# Sheet2.net
KiCad netlist of a schematic drawn in Altium Designer
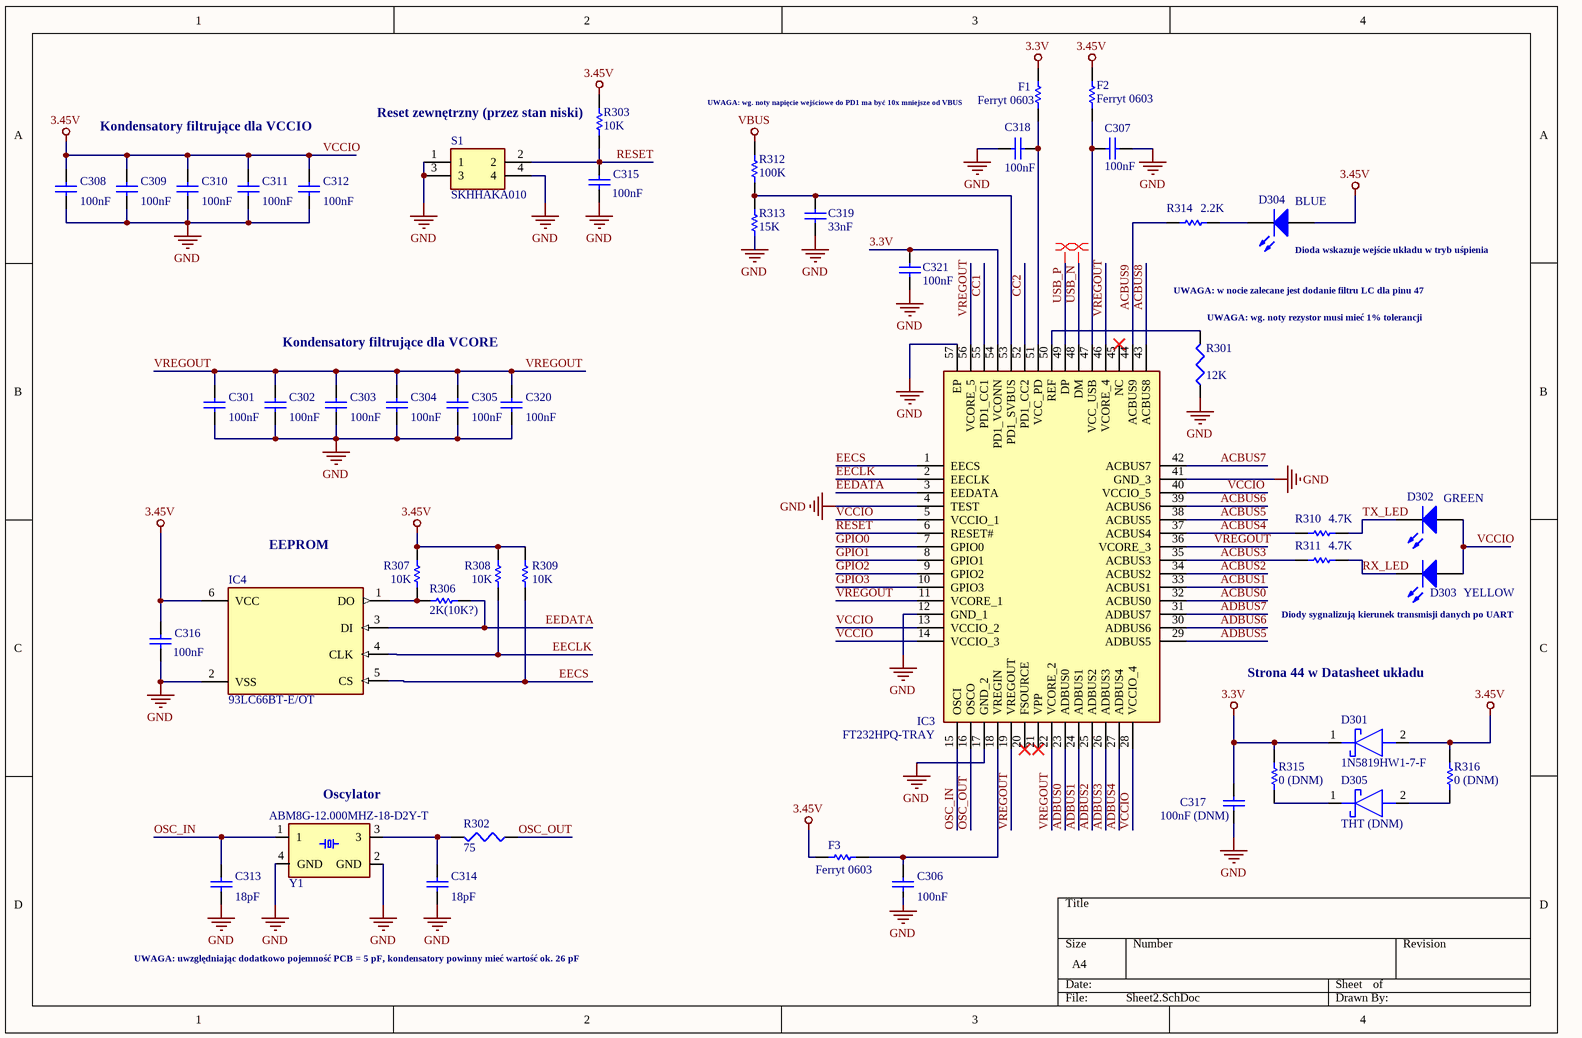
[diagram p0: Sheet2.SchDoc]

(export (version "E")
  (design (tool "Eeschema 10.0.6"))
  (components
    (comp (ref "C301")
      (value "100nF")
      (footprint "1608[0603]")
      (description "Capacitor (Semiconductor SIM Model)")
      (fields (field (name "Comment") "Cap Semi") (field (name "PUBLISHER") "Altium Limited"))
      (libsource (lib "Miscellaneous Devices") (part "Cap Semi"))
    )
    (comp (ref "C302")
      (value "100nF")
      (footprint "1608[0603]")
      (description "Capacitor (Semiconductor SIM Model)")
      (fields (field (name "Comment") "Cap Semi") (field (name "PUBLISHER") "Altium Limited"))
      (libsource (lib "Miscellaneous Devices") (part "Cap Semi"))
    )
    (comp (ref "C303")
      (value "100nF")
      (footprint "1608[0603]")
      (description "Capacitor (Semiconductor SIM Model)")
      (fields (field (name "Comment") "Cap Semi") (field (name "PUBLISHER") "Altium Limited"))
      (libsource (lib "Miscellaneous Devices") (part "Cap Semi"))
    )
    (comp (ref "C304")
      (value "100nF")
      (footprint "1608[0603]")
      (description "Capacitor (Semiconductor SIM Model)")
      (fields (field (name "Comment") "Cap Semi") (field (name "PUBLISHER") "Altium Limited"))
      (libsource (lib "Miscellaneous Devices") (part "Cap Semi"))
    )
    (comp (ref "C305")
      (value "100nF")
      (footprint "1608[0603]")
      (description "Capacitor (Semiconductor SIM Model)")
      (fields (field (name "Comment") "Cap Semi") (field (name "PUBLISHER") "Altium Limited"))
      (libsource (lib "Miscellaneous Devices") (part "Cap Semi"))
    )
    (comp (ref "C306")
      (value "100nF")
      (footprint "1608[0603]")
      (description "Capacitor (Semiconductor SIM Model)")
      (fields (field (name "Comment") "Cap Semi") (field (name "PUBLISHER") "Altium Limited"))
      (libsource (lib "Miscellaneous Devices") (part "Cap Semi"))
    )
    (comp (ref "C307")
      (value "100nF")
      (footprint "1608[0603]")
      (description "Capacitor (Semiconductor SIM Model)")
      (fields (field (name "Comment") "Cap Semi") (field (name "PUBLISHER") "Altium Limited"))
      (libsource (lib "Miscellaneous Devices") (part "Cap Semi"))
    )
    (comp (ref "C308")
      (value "100nF")
      (footprint "1608[0603]")
      (description "Capacitor (Semiconductor SIM Model)")
      (fields (field (name "Comment") "Cap Semi") (field (name "PUBLISHER") "Altium Limited"))
      (libsource (lib "Miscellaneous Devices") (part "Cap Semi"))
    )
    (comp (ref "C309")
      (value "100nF")
      (footprint "1608[0603]")
      (description "Capacitor (Semiconductor SIM Model)")
      (fields (field (name "Comment") "Cap Semi") (field (name "PUBLISHER") "Altium Limited"))
      (libsource (lib "Miscellaneous Devices") (part "Cap Semi"))
    )
    (comp (ref "C310")
      (value "100nF")
      (footprint "1608[0603]")
      (description "Capacitor (Semiconductor SIM Model)")
      (fields (field (name "Comment") "Cap Semi") (field (name "PUBLISHER") "Altium Limited"))
      (libsource (lib "Miscellaneous Devices") (part "Cap Semi"))
    )
    (comp (ref "C311")
      (value "100nF")
      (footprint "1608[0603]")
      (description "Capacitor (Semiconductor SIM Model)")
      (fields (field (name "Comment") "Cap Semi") (field (name "PUBLISHER") "Altium Limited"))
      (libsource (lib "Miscellaneous Devices") (part "Cap Semi"))
    )
    (comp (ref "C312")
      (value "100nF")
      (footprint "1608[0603]")
      (description "Capacitor (Semiconductor SIM Model)")
      (fields (field (name "Comment") "Cap Semi") (field (name "PUBLISHER") "Altium Limited"))
      (libsource (lib "Miscellaneous Devices") (part "Cap Semi"))
    )
    (comp (ref "C313")
      (value "18pF")
      (footprint "1608[0603]")
      (description "Capacitor (Semiconductor SIM Model)")
      (fields (field (name "Comment") "Cap Semi") (field (name "PUBLISHER") "Altium Limited"))
      (libsource (lib "Miscellaneous Devices") (part "Cap Semi"))
    )
    (comp (ref "C314")
      (value "18pF")
      (footprint "1608[0603]")
      (description "Capacitor (Semiconductor SIM Model)")
      (fields (field (name "Comment") "Cap Semi") (field (name "PUBLISHER") "Altium Limited"))
      (libsource (lib "Miscellaneous Devices") (part "Cap Semi"))
    )
    (comp (ref "C315")
      (value "100nF")
      (footprint "1608[0603]")
      (description "Capacitor (Semiconductor SIM Model)")
      (fields (field (name "Comment") "Cap Semi") (field (name "PUBLISHER") "Altium Limited"))
      (libsource (lib "Miscellaneous Devices") (part "Cap Semi"))
    )
    (comp (ref "C316")
      (value "100nF")
      (footprint "1608[0603]")
      (description "Capacitor (Semiconductor SIM Model)")
      (fields (field (name "Comment") "Cap Semi") (field (name "PUBLISHER") "Altium Limited"))
      (libsource (lib "Miscellaneous Devices") (part "Cap Semi"))
    )
    (comp (ref "C317")
      (value "100nF (DNM)")
      (footprint "1608[0603]")
      (description "Capacitor (Semiconductor SIM Model)")
      (fields (field (name "Comment") "Cap Semi") (field (name "PUBLISHER") "Altium Limited"))
      (libsource (lib "Miscellaneous Devices") (part "Cap Semi"))
    )
    (comp (ref "C318")
      (value "100nF")
      (footprint "1608[0603]")
      (description "Capacitor (Semiconductor SIM Model)")
      (fields (field (name "Comment") "Cap Semi") (field (name "PUBLISHER") "Altium Limited"))
      (libsource (lib "Miscellaneous Devices") (part "Cap Semi"))
    )
    (comp (ref "C319")
      (value "33nF")
      (footprint "1608[0603]")
      (description "Capacitor (Semiconductor SIM Model)")
      (fields (field (name "Comment") "Cap Semi") (field (name "PUBLISHER") "Altium Limited"))
      (libsource (lib "Miscellaneous Devices") (part "Cap Semi"))
    )
    (comp (ref "C320")
      (value "100nF")
      (footprint "1608[0603]")
      (description "Capacitor (Semiconductor SIM Model)")
      (fields (field (name "Comment") "Cap Semi") (field (name "PUBLISHER") "Altium Limited"))
      (libsource (lib "Miscellaneous Devices") (part "Cap Semi"))
    )
    (comp (ref "C321")
      (value "100nF")
      (footprint "1608[0603]")
      (description "Capacitor (Semiconductor SIM Model)")
      (fields (field (name "Comment") "Cap Semi") (field (name "PUBLISHER") "Altium Limited"))
      (libsource (lib "Miscellaneous Devices") (part "Cap Semi"))
    )
    (comp (ref "D301")
      (value "1N5819HW1-7-F")
      (footprint "SODFL3518X115N")
      (description "Schottky Diode")
      (fields (field (name "MOUSER PART NUMBER") "621-1N5819HW1-7-F"))
      (libsource (lib "Schlib1") (part "1N5819HW1-7-F"))
    )
    (comp (ref "D302")
      (value "GREEN")
      (footprint "LEDC2012X80N")
      (description "Typical RED, GREEN, YELLOW, AMBER GaAs LED")
      (fields (field (name "PUBLISHER") "Altium Limited"))
      (libsource (lib "Miscellaneous Devices") (part "LED2"))
    )
    (comp (ref "D303")
      (value "YELLOW")
      (footprint "LEDC2012X80N")
      (description "Typical RED, GREEN, YELLOW, AMBER GaAs LED")
      (fields (field (name "PUBLISHER") "Altium Limited"))
      (libsource (lib "Miscellaneous Devices") (part "LED2"))
    )
    (comp (ref "D304")
      (value "BLUE")
      (footprint "LEDC2012X80N")
      (description "Typical RED, GREEN, YELLOW, AMBER GaAs LED")
      (fields (field (name "PUBLISHER") "Altium Limited"))
      (libsource (lib "Miscellaneous Devices") (part "LED2"))
    )
    (comp (ref "D305")
      (value "THT (DNM)")
      (footprint "DIOAD1796W86L628D292")
      (description "Schottky Diode")
      (fields
        (field (name "MANUFACTURER_PART_NUMBER") "1N5819HW1-7-F")
        (field (name "MOUSER PART NUMBER") "621-1N5819HW1-7-F")
      )
      (libsource (lib "Schlib1") (part "1N5819HW1-7-F"))
    )
    (comp (ref "F1")
      (value "Ferryt 0603")
      (footprint "RESC1608X55N")
      (description "Small resistor symbol 0603")
      (fields
        (field (name "MANUFACTURER") "Panasonic")
        (field (name "MANUFACTURER PART NUMBER") "ERJ-2GEJ510X")
      )
      (libsource (lib "Schlib1") (part "Resistor 0603"))
    )
    (comp (ref "F2")
      (value "Ferryt 0603")
      (footprint "RESC1608X55N")
      (description "Small resistor symbol 0603")
      (fields
        (field (name "MANUFACTURER") "Panasonic")
        (field (name "MANUFACTURER PART NUMBER") "ERJ-2GEJ510X")
      )
      (libsource (lib "Schlib1") (part "Resistor 0603"))
    )
    (comp (ref "F3")
      (value "Ferryt 0603")
      (footprint "RESC1608X55N")
      (description "Small resistor symbol 0603")
      (fields
        (field (name "MANUFACTURER") "Panasonic")
        (field (name "MANUFACTURER PART NUMBER") "ERJ-2GEJ510X")
      )
      (libsource (lib "Schlib1") (part "Resistor 0603"))
    )
    (comp (ref "IC3")
      (value "FT232HPQ-TRAY")
      (footprint "QFN50P800X800X90-57N-D")
      (description "Integrated Circuit")
      (fields (field (name "MOUSER PART NUMBER") "895-FT232HPQ-TRAY"))
      (libsource (lib "Schlib1") (part "FT232HPQ-TRAY"))
    )
    (comp (ref "IC4")
      (value "93LC66BT-E/OT")
      (footprint "SOT95P280X145-6N")
      (description "Microwire Compatible Serial EEPROM")
      (libsource (lib "Schlib1") (part "93LC66BT-E/OT"))
    )
    (comp (ref "R301")
      (value "12K")
      (footprint "RESC1608X55N")
      (description "Resistor")
      (fields (field (name "Comment") "Res3") (field (name "PUBLISHER") "Altium Limited"))
      (libsource (lib "Miscellaneous Devices") (part "Res3"))
    )
    (comp (ref "R302")
      (value "75")
      (footprint "RESC1608X55N")
      (description "Resistor")
      (fields (field (name "Comment") "Res3") (field (name "PUBLISHER") "Altium Limited"))
      (libsource (lib "Miscellaneous Devices") (part "Res3"))
    )
    (comp (ref "R303")
      (value "10K")
      (footprint "RESC1608X55N")
      (description "Small resistor symbol 0603")
      (fields
        (field (name "MANUFACTURER") "Panasonic")
        (field (name "MANUFACTURER PART NUMBER") "ERJ-2GEJ510X")
      )
      (libsource (lib "Schlib1") (part "Resistor 0603"))
    )
    (comp (ref "R306")
      (value "2K(10K?)")
      (footprint "RESC1608X55N")
      (description "Small resistor symbol 0603")
      (fields
        (field (name "MANUFACTURER") "Panasonic")
        (field (name "MANUFACTURER PART NUMBER") "ERJ-2GEJ510X")
      )
      (libsource (lib "Schlib1") (part "Resistor 0603"))
    )
    (comp (ref "R307")
      (value "10K")
      (footprint "RESC1608X55N")
      (description "Small resistor symbol 0603")
      (fields
        (field (name "MANUFACTURER") "Panasonic")
        (field (name "MANUFACTURER PART NUMBER") "ERJ-2GEJ510X")
      )
      (libsource (lib "Schlib1") (part "Resistor 0603"))
    )
    (comp (ref "R308")
      (value "10K")
      (footprint "RESC1608X55N")
      (description "Small resistor symbol 0603")
      (fields
        (field (name "MANUFACTURER") "Panasonic")
        (field (name "MANUFACTURER PART NUMBER") "ERJ-2GEJ510X")
      )
      (libsource (lib "Schlib1") (part "Resistor 0603"))
    )
    (comp (ref "R309")
      (value "10K")
      (footprint "RESC1608X55N")
      (description "Small resistor symbol 0603")
      (fields
        (field (name "MANUFACTURER") "Panasonic")
        (field (name "MANUFACTURER PART NUMBER") "ERJ-2GEJ510X")
      )
      (libsource (lib "Schlib1") (part "Resistor 0603"))
    )
    (comp (ref "R310")
      (value "4.7K")
      (footprint "RESC1608X55N")
      (description "Small resistor symbol 0603")
      (fields
        (field (name "MANUFACTURER") "Panasonic")
        (field (name "MANUFACTURER PART NUMBER") "ERJ-2GEJ510X")
      )
      (libsource (lib "Schlib1") (part "Resistor 0603"))
    )
    (comp (ref "R311")
      (value "4.7K")
      (footprint "RESC1608X55N")
      (description "Small resistor symbol 0603")
      (fields
        (field (name "MANUFACTURER") "Panasonic")
        (field (name "MANUFACTURER PART NUMBER") "ERJ-2GEJ510X")
      )
      (libsource (lib "Schlib1") (part "Resistor 0603"))
    )
    (comp (ref "R312")
      (value "100K")
      (footprint "RESC1608X55N")
      (description "Small resistor symbol 0603")
      (fields
        (field (name "MANUFACTURER") "Panasonic")
        (field (name "MANUFACTURER PART NUMBER") "ERJ-2GEJ510X")
      )
      (libsource (lib "Schlib1") (part "Resistor 0603"))
    )
    (comp (ref "R313")
      (value "15K")
      (footprint "RESC1608X55N")
      (description "Small resistor symbol 0603")
      (fields
        (field (name "MANUFACTURER") "Panasonic")
        (field (name "MANUFACTURER PART NUMBER") "ERJ-2GEJ510X")
      )
      (libsource (lib "Schlib1") (part "Resistor 0603"))
    )
    (comp (ref "R314")
      (value "2.2K")
      (footprint "RESC1608X55N")
      (description "Small resistor symbol 0603")
      (fields
        (field (name "MANUFACTURER") "Panasonic")
        (field (name "MANUFACTURER PART NUMBER") "ERJ-2GEJ510X")
      )
      (libsource (lib "Schlib1") (part "Resistor 0603"))
    )
    (comp (ref "R315")
      (value "0 (DNM)")
      (footprint "RESC1608X55N")
      (description "Small resistor symbol 0603")
      (fields
        (field (name "MANUFACTURER") "Panasonic")
        (field (name "MANUFACTURER PART NUMBER") "ERJ-2GEJ510X")
      )
      (libsource (lib "Schlib1") (part "Resistor 0603"))
    )
    (comp (ref "R316")
      (value "0 (DNM)")
      (footprint "RESC1608X55N")
      (description "Small resistor symbol 0603")
      (fields
        (field (name "MANUFACTURER") "Panasonic")
        (field (name "MANUFACTURER PART NUMBER") "ERJ-2GEJ510X")
      )
      (libsource (lib "Schlib1") (part "Resistor 0603"))
    )
    (comp (ref "S1")
      (value "SKHHAKA010")
      (footprint "SKHHALA010")
      (description "Switch")
      (fields (field (name "MOUSER PART NUMBER") "688-SKHHAK"))
      (libsource (lib "Schlib1") (part "SKHHAKA010"))
    )
    (comp (ref "Y1")
      (value "ABM8G-12.000MHZ-18-D2Y-T")
      (footprint "OSCSC320X250X100N")
      (description "12MHz Â±20ppm Crystal 18pF 120 Ohms 4-SMD, No Lead")
      (fields (field (name "MF") "Abracon") (field (name "DIGI-KEY_PART_NUMBER") "535-10261-1-ND"))
      (libsource (lib "Schlib1") (part "ABM8G-12.000MHZ-18-D2Y-T"))
    )
  )
  (nets
    (net (code "1") (name "/ACBUS0") (class "Default")
      (node (ref "IC3") (pin "32") (pinfunction "ACBUS0_32") (pintype "passive"))
    )
    (net (code "2") (name "/ACBUS1") (class "Default")
      (node (ref "IC3") (pin "33") (pinfunction "ACBUS1_33") (pintype "passive"))
    )
    (net (code "3") (name "/ACBUS2") (class "Default")
      (node (ref "IC3") (pin "34") (pinfunction "ACBUS2_34") (pintype "passive"))
    )
    (net (code "4") (name "/ACBUS3") (class "Default")
      (node (ref "IC3") (pin "35") (pinfunction "ACBUS3_35") (pintype "passive"))
      (node (ref "R311") (pin "1") (pinfunction "1_1") (pintype "passive"))
    )
    (net (code "5") (name "/ACBUS4") (class "Default")
      (node (ref "IC3") (pin "37") (pinfunction "ACBUS4_37") (pintype "passive"))
      (node (ref "R310") (pin "1") (pinfunction "1_1") (pintype "passive"))
    )
    (net (code "6") (name "/ACBUS5") (class "Default")
      (node (ref "IC3") (pin "38") (pinfunction "ACBUS5_38") (pintype "passive"))
    )
    (net (code "7") (name "/ACBUS6") (class "Default")
      (node (ref "IC3") (pin "39") (pinfunction "ACBUS6_39") (pintype "passive"))
    )
    (net (code "8") (name "/ACBUS7") (class "Default")
      (node (ref "IC3") (pin "42") (pinfunction "ACBUS7_42") (pintype "passive"))
    )
    (net (code "9") (name "/ACBUS8") (class "Default")
      (node (ref "IC3") (pin "43") (pinfunction "ACBUS8_43") (pintype "passive"))
    )
    (net (code "10") (name "/ACBUS9") (class "Default")
      (node (ref "IC3") (pin "44") (pinfunction "ACBUS9_44") (pintype "passive"))
      (node (ref "R314") (pin "1") (pinfunction "1_1") (pintype "passive"))
    )
    (net (code "11") (name "/ADBUS0") (class "Default")
      (node (ref "IC3") (pin "23") (pinfunction "ADBUS0_23") (pintype "passive"))
    )
    (net (code "12") (name "/ADBUS1") (class "Default")
      (node (ref "IC3") (pin "24") (pinfunction "ADBUS1_24") (pintype "passive"))
    )
    (net (code "13") (name "/ADBUS2") (class "Default")
      (node (ref "IC3") (pin "25") (pinfunction "ADBUS2_25") (pintype "passive"))
    )
    (net (code "14") (name "/ADBUS3") (class "Default")
      (node (ref "IC3") (pin "26") (pinfunction "ADBUS3_26") (pintype "passive"))
    )
    (net (code "15") (name "/ADBUS4") (class "Default")
      (node (ref "IC3") (pin "27") (pinfunction "ADBUS4_27") (pintype "passive"))
    )
    (net (code "16") (name "/ADBUS5") (class "Default")
      (node (ref "IC3") (pin "29") (pinfunction "ADBUS5_29") (pintype "passive"))
    )
    (net (code "17") (name "/ADBUS6") (class "Default")
      (node (ref "IC3") (pin "30") (pinfunction "ADBUS6_30") (pintype "passive"))
    )
    (net (code "18") (name "/ADBUS7") (class "Default")
      (node (ref "IC3") (pin "31") (pinfunction "ADBUS7_31") (pintype "passive"))
    )
    (net (code "19") (name "/CC1") (class "Default")
      (node (ref "IC3") (pin "55") (pinfunction "PD1_CC1_55") (pintype "passive"))
    )
    (net (code "20") (name "/CC2") (class "Default")
      (node (ref "IC3") (pin "52") (pinfunction "PD1_CC2_52") (pintype "passive"))
    )
    (net (code "21") (name "/EECLK") (class "Default")
      (node (ref "IC3") (pin "2") (pinfunction "EECLK_2") (pintype "passive"))
      (node (ref "IC4") (pin "4") (pinfunction "CLK_4") (pintype "input"))
      (node (ref "R308") (pin "2") (pinfunction "2_2") (pintype "passive"))
    )
    (net (code "22") (name "/EECS") (class "Default")
      (node (ref "IC3") (pin "1") (pinfunction "EECS_1") (pintype "passive"))
      (node (ref "IC4") (pin "5") (pinfunction "CS_5") (pintype "input"))
      (node (ref "R309") (pin "2") (pinfunction "2_2") (pintype "passive"))
    )
    (net (code "23") (name "/EEDATA") (class "Default")
      (node (ref "IC3") (pin "3") (pinfunction "EEDATA_3") (pintype "passive"))
      (node (ref "IC4") (pin "3") (pinfunction "DI_3") (pintype "input"))
      (node (ref "R306") (pin "2") (pinfunction "2_2") (pintype "passive"))
    )
    (net (code "24") (name "/GPIO0") (class "Default")
      (node (ref "IC3") (pin "7") (pinfunction "GPIO0_7") (pintype "passive"))
    )
    (net (code "25") (name "/GPIO1") (class "Default")
      (node (ref "IC3") (pin "8") (pinfunction "GPIO1_8") (pintype "passive"))
    )
    (net (code "26") (name "/GPIO2") (class "Default")
      (node (ref "IC3") (pin "9") (pinfunction "GPIO2_9") (pintype "passive"))
    )
    (net (code "27") (name "/GPIO3") (class "Default")
      (node (ref "IC3") (pin "10") (pinfunction "GPIO3_10") (pintype "passive"))
    )
    (net (code "28") (name "/OSC_IN") (class "Default")
      (node (ref "C313") (pin "2") (pinfunction "2_2") (pintype "passive"))
      (node (ref "IC3") (pin "15") (pinfunction "OSCI_15") (pintype "passive"))
      (node (ref "Y1") (pin "1") (pinfunction "1_1") (pintype "passive"))
    )
    (net (code "29") (name "/OSC_OUT") (class "Default")
      (node (ref "IC3") (pin "16") (pinfunction "OSCO_16") (pintype "passive"))
      (node (ref "R302") (pin "1") (pinfunction "1_1") (pintype "passive"))
    )
    (net (code "30") (name "/RESET") (class "Default")
      (node (ref "C315") (pin "1") (pinfunction "1_1") (pintype "passive"))
      (node (ref "IC3") (pin "6") (pinfunction "RESET#_6") (pintype "passive"))
      (node (ref "R303") (pin "1") (pinfunction "1_1") (pintype "passive"))
      (node (ref "S1") (pin "2") (pinfunction "2_2") (pintype "passive"))
    )
    (net (code "31") (name "/RX_LED") (class "Default")
      (node (ref "D303") (pin "2") (pinfunction "K_2") (pintype "passive"))
      (node (ref "R311") (pin "2") (pinfunction "2_2") (pintype "passive"))
    )
    (net (code "32") (name "/TX_LED") (class "Default")
      (node (ref "D302") (pin "2") (pinfunction "K_2") (pintype "passive"))
      (node (ref "R310") (pin "2") (pinfunction "2_2") (pintype "passive"))
    )
    (net (code "33") (name "/USB_N") (class "Default")
      (node (ref "IC3") (pin "48") (pinfunction "DM_48") (pintype "passive"))
    )
    (net (code "34") (name "/USB_P") (class "Default")
      (node (ref "IC3") (pin "49") (pinfunction "DP_49") (pintype "passive"))
    )
    (net (code "35") (name "/VREGOUT") (class "Default")
      (node (ref "C301") (pin "2") (pinfunction "2_2") (pintype "passive"))
      (node (ref "C302") (pin "2") (pinfunction "2_2") (pintype "passive"))
      (node (ref "C303") (pin "2") (pinfunction "2_2") (pintype "passive"))
      (node (ref "C304") (pin "2") (pinfunction "2_2") (pintype "passive"))
      (node (ref "C305") (pin "2") (pinfunction "2_2") (pintype "passive"))
      (node (ref "C320") (pin "2") (pinfunction "2_2") (pintype "passive"))
      (node (ref "IC3") (pin "11") (pinfunction "VCORE_1_11") (pintype "passive"))
      (node (ref "IC3") (pin "19") (pinfunction "VREGOUT_19") (pintype "passive"))
      (node (ref "IC3") (pin "22") (pinfunction "VCORE_2_22") (pintype "passive"))
      (node (ref "IC3") (pin "36") (pinfunction "VCORE_3_36") (pintype "passive"))
      (node (ref "IC3") (pin "46") (pinfunction "VCORE_4_46") (pintype "passive"))
      (node (ref "IC3") (pin "56") (pinfunction "VCORE_5_56") (pintype "passive"))
    )
    (net (code "36") (name "3.3V") (class "Default")
      (node (ref "C317") (pin "1") (pinfunction "1_1") (pintype "passive"))
      (node (ref "C321") (pin "2") (pinfunction "2_2") (pintype "passive"))
      (node (ref "D301") (pin "1") (pinfunction "K_1") (pintype "passive"))
      (node (ref "F1") (pin "2") (pinfunction "2_2") (pintype "passive"))
      (node (ref "IC3") (pin "54") (pinfunction "PD1_VCONN_54") (pintype "passive"))
      (node (ref "R315") (pin "2") (pinfunction "2_2") (pintype "passive"))
    )
    (net (code "37") (name "3.45V") (class "Default")
      (node (ref "C308") (pin "2") (pinfunction "2_2") (pintype "passive"))
      (node (ref "C309") (pin "2") (pinfunction "2_2") (pintype "passive"))
      (node (ref "C310") (pin "2") (pinfunction "2_2") (pintype "passive"))
      (node (ref "C311") (pin "2") (pinfunction "2_2") (pintype "passive"))
      (node (ref "C312") (pin "2") (pinfunction "2_2") (pintype "passive"))
      (node (ref "C316") (pin "1") (pinfunction "1_1") (pintype "passive"))
      (node (ref "D301") (pin "2") (pinfunction "A_2") (pintype "passive"))
      (node (ref "D302") (pin "1") (pinfunction "A_1") (pintype "passive"))
      (node (ref "D303") (pin "1") (pinfunction "A_1") (pintype "passive"))
      (node (ref "D304") (pin "1") (pinfunction "A_1") (pintype "passive"))
      (node (ref "F2") (pin "1") (pinfunction "1_1") (pintype "passive"))
      (node (ref "F3") (pin "1") (pinfunction "1_1") (pintype "passive"))
      (node (ref "IC3") (pin "13") (pinfunction "VCCIO_2_13") (pintype "passive"))
      (node (ref "IC3") (pin "14") (pinfunction "VCCIO_3_14") (pintype "passive"))
      (node (ref "IC3") (pin "28") (pinfunction "VCCIO_4_28") (pintype "passive"))
      (node (ref "IC3") (pin "40") (pinfunction "VCCIO_5_40") (pintype "passive"))
      (node (ref "IC3") (pin "5") (pinfunction "VCCIO_1_5") (pintype "passive"))
      (node (ref "IC4") (pin "6") (pinfunction "VCC_6") (pintype "power_in"))
      (node (ref "R303") (pin "2") (pinfunction "2_2") (pintype "passive"))
      (node (ref "R307") (pin "1") (pinfunction "1_1") (pintype "passive"))
      (node (ref "R308") (pin "1") (pinfunction "1_1") (pintype "passive"))
      (node (ref "R309") (pin "1") (pinfunction "1_1") (pintype "passive"))
      (node (ref "R316") (pin "2") (pinfunction "2_2") (pintype "passive"))
    )
    (net (code "38") (name "GND") (class "Default")
      (node (ref "C301") (pin "1") (pinfunction "1_1") (pintype "passive"))
      (node (ref "C302") (pin "1") (pinfunction "1_1") (pintype "passive"))
      (node (ref "C303") (pin "1") (pinfunction "1_1") (pintype "passive"))
      (node (ref "C304") (pin "1") (pinfunction "1_1") (pintype "passive"))
      (node (ref "C305") (pin "1") (pinfunction "1_1") (pintype "passive"))
      (node (ref "C306") (pin "1") (pinfunction "1_1") (pintype "passive"))
      (node (ref "C307") (pin "2") (pinfunction "2_2") (pintype "passive"))
      (node (ref "C308") (pin "1") (pinfunction "1_1") (pintype "passive"))
      (node (ref "C309") (pin "1") (pinfunction "1_1") (pintype "passive"))
      (node (ref "C310") (pin "1") (pinfunction "1_1") (pintype "passive"))
      (node (ref "C311") (pin "1") (pinfunction "1_1") (pintype "passive"))
      (node (ref "C312") (pin "1") (pinfunction "1_1") (pintype "passive"))
      (node (ref "C313") (pin "1") (pinfunction "1_1") (pintype "passive"))
      (node (ref "C314") (pin "1") (pinfunction "1_1") (pintype "passive"))
      (node (ref "C315") (pin "2") (pinfunction "2_2") (pintype "passive"))
      (node (ref "C316") (pin "2") (pinfunction "2_2") (pintype "passive"))
      (node (ref "C317") (pin "2") (pinfunction "2_2") (pintype "passive"))
      (node (ref "C318") (pin "1") (pinfunction "1_1") (pintype "passive"))
      (node (ref "C319") (pin "1") (pinfunction "1_1") (pintype "passive"))
      (node (ref "C320") (pin "1") (pinfunction "1_1") (pintype "passive"))
      (node (ref "C321") (pin "1") (pinfunction "1_1") (pintype "passive"))
      (node (ref "IC3") (pin "12") (pinfunction "GND_1_12") (pintype "passive"))
      (node (ref "IC3") (pin "17") (pinfunction "GND_2_17") (pintype "passive"))
      (node (ref "IC3") (pin "4") (pinfunction "TEST_4") (pintype "passive"))
      (node (ref "IC3") (pin "41") (pinfunction "GND_3_41") (pintype "passive"))
      (node (ref "IC3") (pin "57") (pinfunction "EP_57") (pintype "passive"))
      (node (ref "IC4") (pin "2") (pinfunction "VSS_2") (pintype "power_in"))
      (node (ref "R301") (pin "1") (pinfunction "1_1") (pintype "passive"))
      (node (ref "R313") (pin "1") (pinfunction "1_1") (pintype "passive"))
      (node (ref "S1") (pin "1") (pinfunction "1_1") (pintype "passive"))
      (node (ref "S1") (pin "3") (pinfunction "3_3") (pintype "passive"))
      (node (ref "S1") (pin "4") (pinfunction "4_4") (pintype "passive"))
      (node (ref "Y1") (pin "2") (pinfunction "GND_2") (pintype "power_in"))
      (node (ref "Y1") (pin "4") (pinfunction "GND_4") (pintype "power_in"))
    )
    (net (code "39") (name "Net-(C314-Pad2)") (class "Default")
      (node (ref "C314") (pin "2") (pinfunction "2_2") (pintype "passive"))
      (node (ref "R302") (pin "2") (pinfunction "2_2") (pintype "passive"))
      (node (ref "Y1") (pin "3") (pinfunction "3_3") (pintype "passive"))
    )
    (net (code "40") (name "Net-(D304-K)") (class "Default")
      (node (ref "D304") (pin "2") (pinfunction "K_2") (pintype "passive"))
      (node (ref "R314") (pin "2") (pinfunction "2_2") (pintype "passive"))
    )
    (net (code "41") (name "Net-(D305-A)") (class "Default")
      (node (ref "D305") (pin "2") (pinfunction "A_2") (pintype "passive"))
      (node (ref "R316") (pin "1") (pinfunction "1_1") (pintype "passive"))
    )
    (net (code "42") (name "Net-(D305-K)") (class "Default")
      (node (ref "D305") (pin "1") (pinfunction "K_1") (pintype "passive"))
      (node (ref "R315") (pin "1") (pinfunction "1_1") (pintype "passive"))
    )
    (net (code "43") (name "Net-(IC3-PD1_SVBUS)") (class "Default")
      (node (ref "C319") (pin "2") (pinfunction "2_2") (pintype "passive"))
      (node (ref "IC3") (pin "53") (pinfunction "PD1_SVBUS_53") (pintype "passive"))
      (node (ref "R312") (pin "1") (pinfunction "1_1") (pintype "passive"))
      (node (ref "R313") (pin "2") (pinfunction "2_2") (pintype "passive"))
    )
    (net (code "44") (name "Net-(IC3-REF)") (class "Default")
      (node (ref "IC3") (pin "50") (pinfunction "REF_50") (pintype "passive"))
      (node (ref "R301") (pin "2") (pinfunction "2_2") (pintype "passive"))
    )
    (net (code "45") (name "Net-(IC3-VCC_PD)") (class "Default")
      (node (ref "C318") (pin "2") (pinfunction "2_2") (pintype "passive"))
      (node (ref "F1") (pin "1") (pinfunction "1_1") (pintype "passive"))
      (node (ref "IC3") (pin "51") (pinfunction "VCC_PD_51") (pintype "passive"))
    )
    (net (code "46") (name "Net-(IC3-VCC_USB)") (class "Default")
      (node (ref "C307") (pin "1") (pinfunction "1_1") (pintype "passive"))
      (node (ref "F2") (pin "2") (pinfunction "2_2") (pintype "passive"))
      (node (ref "IC3") (pin "47") (pinfunction "VCC_USB_47") (pintype "passive"))
    )
    (net (code "47") (name "Net-(IC3-VREGIN)") (class "Default")
      (node (ref "C306") (pin "2") (pinfunction "2_2") (pintype "passive"))
      (node (ref "F3") (pin "2") (pinfunction "2_2") (pintype "passive"))
      (node (ref "IC3") (pin "18") (pinfunction "VREGIN_18") (pintype "passive"))
    )
    (net (code "48") (name "Net-(IC4-DO)") (class "Default")
      (node (ref "IC4") (pin "1") (pinfunction "DO_1") (pintype "output"))
      (node (ref "R306") (pin "1") (pinfunction "1_1") (pintype "passive"))
      (node (ref "R307") (pin "2") (pinfunction "2_2") (pintype "passive"))
    )
    (net (code "49") (name "VBUS") (class "Default")
      (node (ref "R312") (pin "2") (pinfunction "2_2") (pintype "passive"))
    )
    (net (code "50") (name "unconnected-(IC3-FSOURCE-Pad20)") (class "Default")
      (node (ref "IC3") (pin "20") (pinfunction "FSOURCE_20") (pintype "passive+no_connect"))
    )
    (net (code "51") (name "unconnected-(IC3-NC-Pad45)") (class "Default")
      (node (ref "IC3") (pin "45") (pinfunction "NC_45") (pintype "passive+no_connect"))
    )
    (net (code "52") (name "unconnected-(IC3-VPP-Pad21)") (class "Default")
      (node (ref "IC3") (pin "21") (pinfunction "VPP_21") (pintype "passive+no_connect"))
    )
  )
)
